# piezo_amp.net
KiCad netlist of a schematic drawn in EAGLE
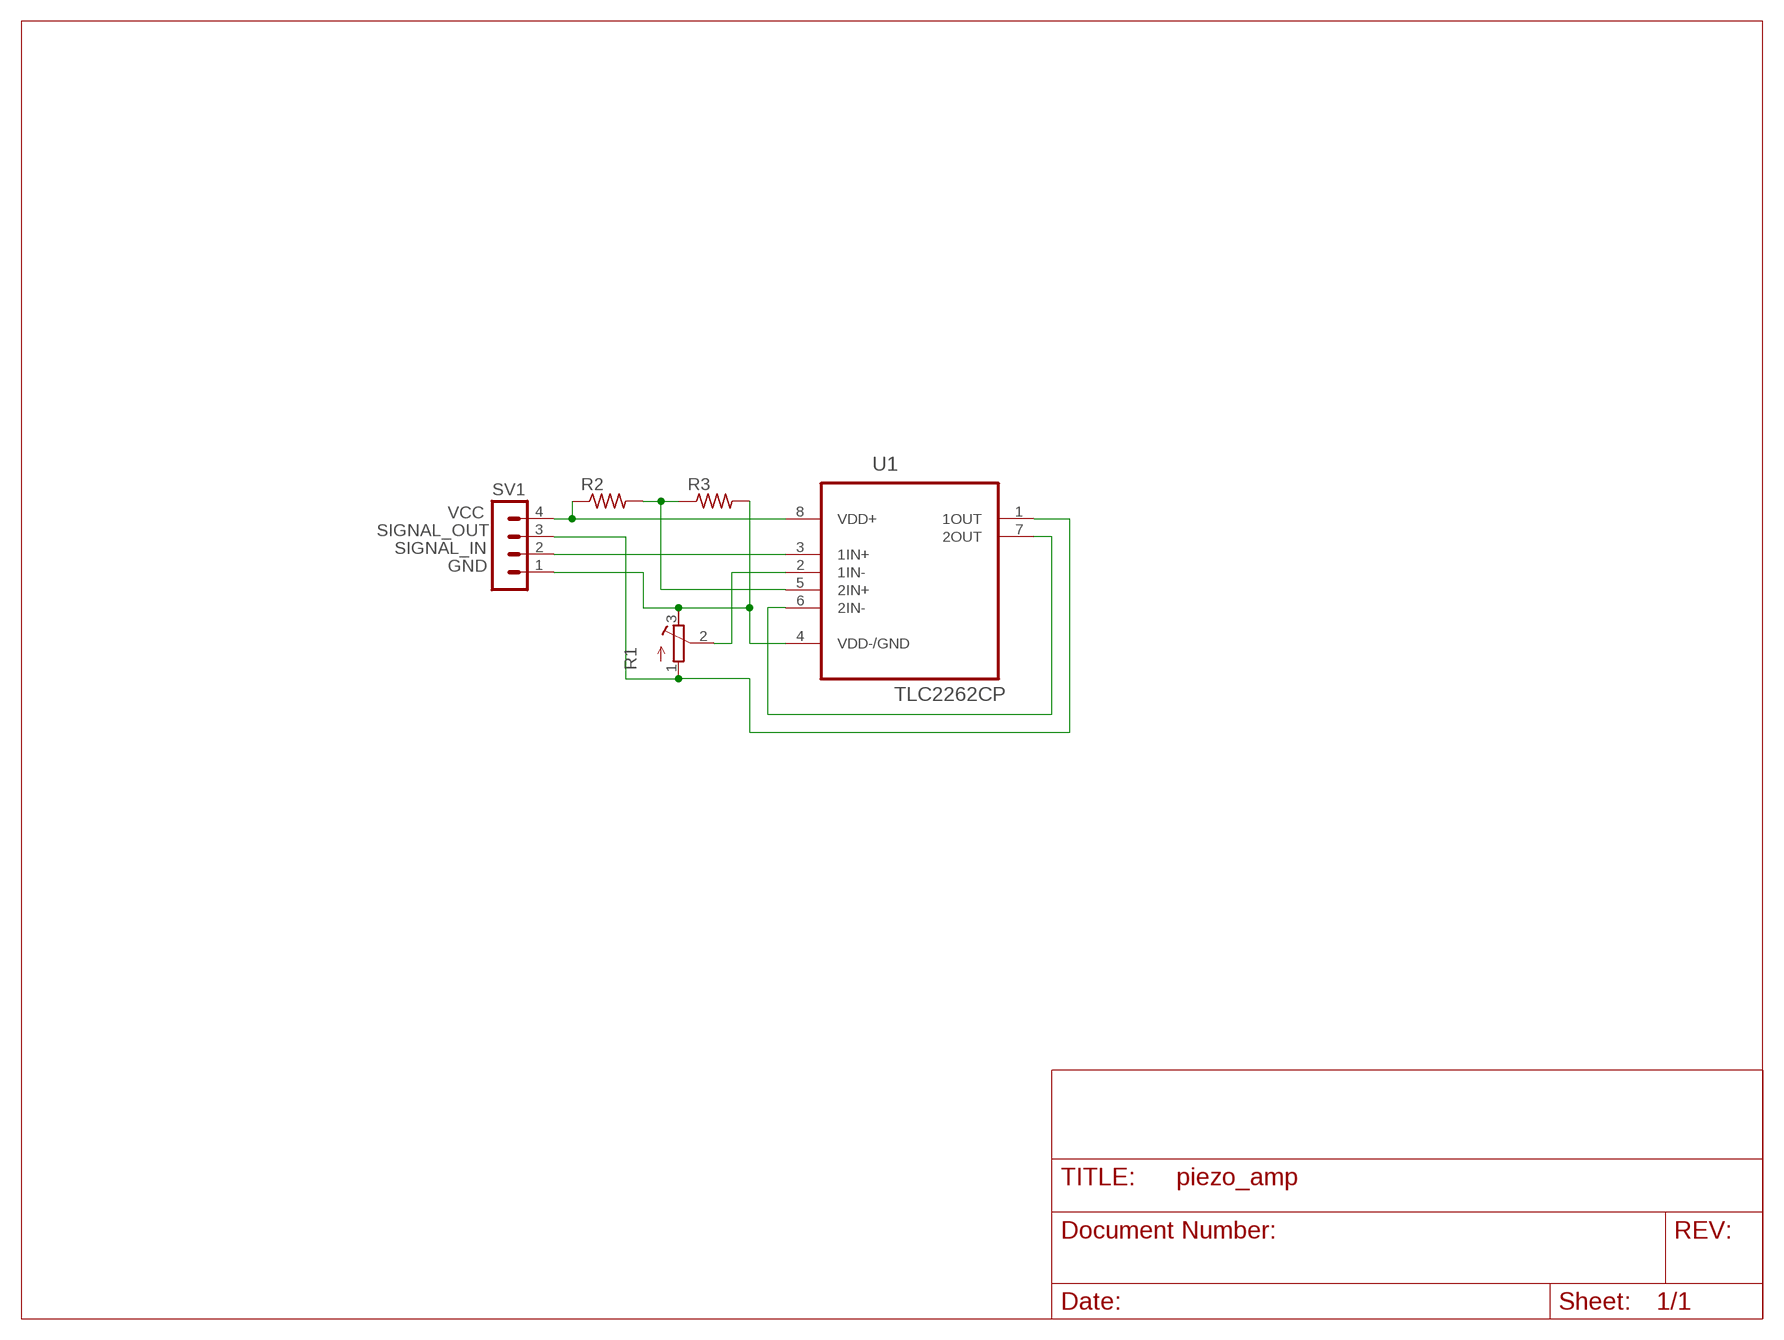
[diagram p0: schematic, sheet 1]

(export (version "E")
  (design (tool "Eeschema 10.0.6"))
  (components
    (comp (ref "R1")
      (value "R-TRIMM3296W")
      (footprint "eagle-import:RTRIM3296W")
      (libsource (lib "eagle-import") (part "R-TRIMM3296W"))
    )
    (comp (ref "R2")
      (value "R-US_0204/5")
      (footprint "eagle-import:0204_5")
      (libsource (lib "eagle-import") (part "R-US_0204/5"))
    )
    (comp (ref "R3")
      (value "R-US_0204/5")
      (footprint "eagle-import:0204_5")
      (libsource (lib "eagle-import") (part "R-US_0204/5"))
    )
    (comp (ref "SV1")
      (value "MA04-1")
      (footprint "eagle-import:MA04-1")
      (libsource (lib "eagle-import") (part "MA04-1"))
    )
    (comp (ref "U1")
      (value "TLC2262CP")
      (footprint "eagle-import:DIP254P762X508-8")
      (libsource (lib "eagle-import") (part "TLC2262CP"))
    )
  )
  (nets
    (net (code "1") (name "/GND") (class "Default")
      (node (ref "R1") (pin "3") (pinfunction "E_3") (pintype "passive"))
      (node (ref "R3") (pin "2") (pinfunction "2_2") (pintype "passive"))
      (node (ref "SV1") (pin "1") (pinfunction "1_1") (pintype "passive"))
      (node (ref "U1") (pin "4") (pinfunction "VDD-/GND_4") (pintype "passive"))
    )
    (net (code "2") (name "/SIGNAL_IN") (class "Default")
      (node (ref "SV1") (pin "2") (pinfunction "2_2") (pintype "passive"))
      (node (ref "U1") (pin "3") (pinfunction "1IN+_3") (pintype "input"))
    )
    (net (code "3") (name "/SIGNAL_OUT") (class "Default")
      (node (ref "R1") (pin "1") (pinfunction "A_1") (pintype "passive"))
      (node (ref "SV1") (pin "3") (pinfunction "3_3") (pintype "passive"))
      (node (ref "U1") (pin "1") (pinfunction "1OUT_1") (pintype "output"))
    )
    (net (code "4") (name "/VCC") (class "Default")
      (node (ref "R2") (pin "1") (pinfunction "1_1") (pintype "passive"))
      (node (ref "SV1") (pin "4") (pinfunction "4_4") (pintype "passive"))
      (node (ref "U1") (pin "8") (pinfunction "VDD+_8") (pintype "power_in"))
    )
    (net (code "5") (name "Net-(R1-S)") (class "Default")
      (node (ref "R1") (pin "2") (pinfunction "S_2") (pintype "passive"))
      (node (ref "U1") (pin "2") (pinfunction "1IN-_2") (pintype "input"))
    )
    (net (code "6") (name "Net-(U1-2IN+)") (class "Default")
      (node (ref "R2") (pin "2") (pinfunction "2_2") (pintype "passive"))
      (node (ref "R3") (pin "1") (pinfunction "1_1") (pintype "passive"))
      (node (ref "U1") (pin "5") (pinfunction "2IN+_5") (pintype "input"))
    )
    (net (code "7") (name "Net-(U1-2IN-)") (class "Default")
      (node (ref "U1") (pin "6") (pinfunction "2IN-_6") (pintype "input"))
      (node (ref "U1") (pin "7") (pinfunction "2OUT_7") (pintype "output"))
    )
  )
)
